# tiny13_charlie4_50mm_boosted_optical_dia.net
KiCad netlist of a schematic drawn in EAGLE
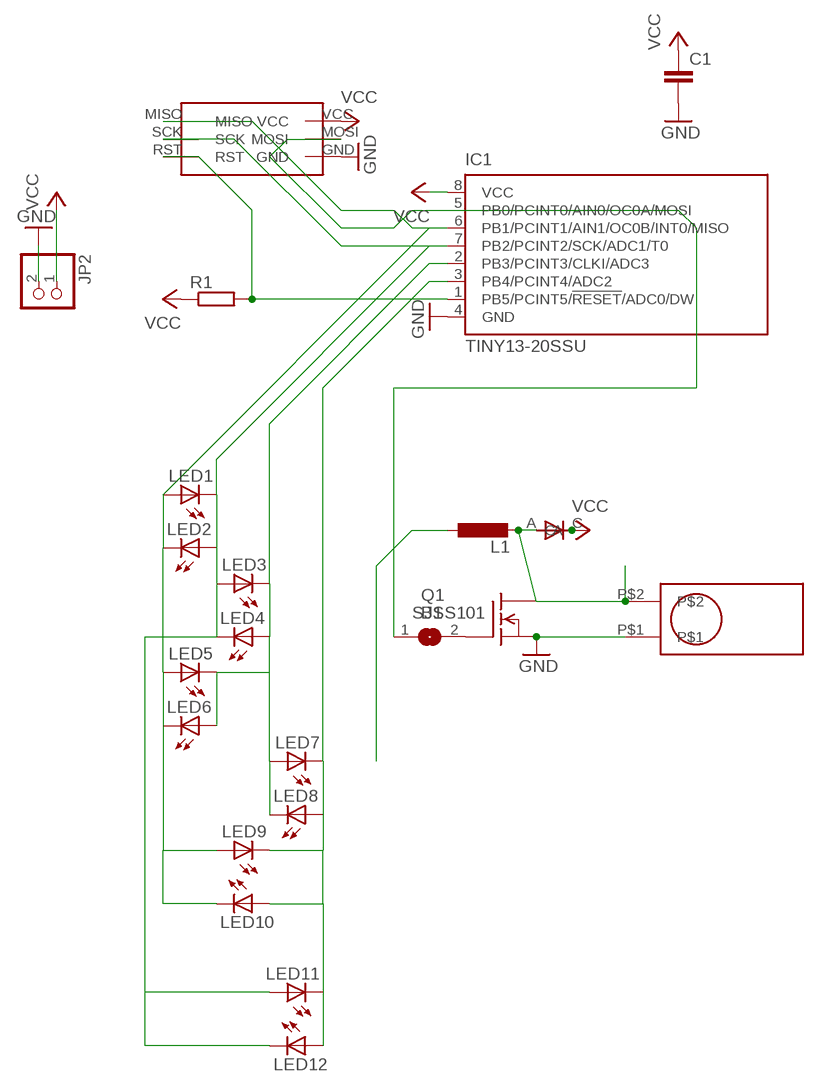
[diagram p0: schematic, sheet 1]

(export (version "E")
  (design (tool "Eeschema 10.0.6"))
  (components
    (comp (ref "C1")
      (value "C-EU025-025X050")
      (footprint "eagle-import:C025-025X050")
      (libsource (lib "eagle-import") (part "C-EU025-025X050"))
    )
    (comp (ref "IC1")
      (value "TINY13-20SSU")
      (footprint "eagle-import:8S1")
      (fields (field (name "MPN") "ATTINY13-20SSU"))
      (libsource (lib "eagle-import") (part "TINY13SSU-20"))
    )
    (comp (ref "JP2")
      (value "PINHD-1X2")
      (footprint "eagle-import:1X02")
      (libsource (lib "eagle-import") (part "PINHD-1X2"))
    )
    (comp (ref "L1")
      (value "L-EU0204/5")
      (footprint "eagle-import:0204_5")
      (libsource (lib "eagle-import") (part "L-EU0204/5"))
    )
    (comp (ref "LED1")
      (value "LED3MM")
      (footprint "eagle-import:LED3MM")
      (libsource (lib "eagle-import") (part "LED3MM"))
    )
    (comp (ref "LED2")
      (value "LED3MM")
      (footprint "eagle-import:LED3MM")
      (libsource (lib "eagle-import") (part "LED3MM"))
    )
    (comp (ref "LED3")
      (value "LED3MM")
      (footprint "eagle-import:LED3MM")
      (libsource (lib "eagle-import") (part "LED3MM"))
    )
    (comp (ref "LED4")
      (value "LED3MM")
      (footprint "eagle-import:LED3MM")
      (libsource (lib "eagle-import") (part "LED3MM"))
    )
    (comp (ref "LED5")
      (value "LED3MM")
      (footprint "eagle-import:LED3MM")
      (libsource (lib "eagle-import") (part "LED3MM"))
    )
    (comp (ref "LED6")
      (value "LED3MM")
      (footprint "eagle-import:LED3MM")
      (libsource (lib "eagle-import") (part "LED3MM"))
    )
    (comp (ref "LED7")
      (value "LED3MM")
      (footprint "eagle-import:LED3MM")
      (libsource (lib "eagle-import") (part "LED3MM"))
    )
    (comp (ref "LED8")
      (value "LED3MM")
      (footprint "eagle-import:LED3MM")
      (libsource (lib "eagle-import") (part "LED3MM"))
    )
    (comp (ref "LED9")
      (value "LED3MM")
      (footprint "eagle-import:LED3MM")
      (libsource (lib "eagle-import") (part "LED3MM"))
    )
    (comp (ref "LED10")
      (value "LED3MM")
      (footprint "eagle-import:LED3MM")
      (libsource (lib "eagle-import") (part "LED3MM"))
    )
    (comp (ref "LED11")
      (value "LED3MM")
      (footprint "eagle-import:LED3MM")
      (libsource (lib "eagle-import") (part "LED3MM"))
    )
    (comp (ref "LED12")
      (value "LED3MM")
      (footprint "eagle-import:LED3MM")
      (libsource (lib "eagle-import") (part "LED3MM"))
    )
    (comp (ref "Q1")
      (value "BSS101")
      (footprint "eagle-import:TO92")
      (libsource (lib "eagle-import") (part "BSS101"))
    )
    (comp (ref "R1")
      (value "R-EU_0204/5")
      (footprint "eagle-import:0204_5")
      (libsource (lib "eagle-import") (part "R-EU_0204/5"))
    )
    (comp (ref "SJ1") (value "SJ") (footprint "eagle-import:SJ") (libsource (lib "eagle-import") (part "SJ")))
    (comp (ref "U$1")
      (value "TILT_SWITCH_MECHANICAL")
      (footprint "eagle-import:TILT_SWITCH_MECHANICAL")
      (libsource (lib "eagle-import") (part "TILT_SWITCH_MECHANICAL"))
    )
    (comp (ref "U$2")
      (value "AVR_ISP_6_PIN_1X6_SMT_CONTACT_PROGRAMMER")
      (footprint "eagle-import:CONTACT_ISP_PROGRAMMER_1X6_ATMEL_2")
      (libsource (lib "eagle-import") (part "AVR_ISP_6_PIN_1X6_SMT_CONTACT_PROGRAMMER"))
    )
    (comp (ref "U$3")
      (value "D-6")
      (footprint "eagle-import:D-7.5")
      (libsource (lib "eagle-import") (part "D-6"))
    )
  )
  (nets
    (net (code "1") (name "GND") (class "Default")
      (node (ref "C1") (pin "2") (pinfunction "2_2") (pintype "passive"))
      (node (ref "IC1") (pin "4") (pinfunction "GND_4") (pintype "power_in"))
      (node (ref "JP2") (pin "2") (pinfunction "2_2") (pintype "passive"))
      (node (ref "Q1") (pin "1") (pinfunction "S_1") (pintype "passive"))
      (node (ref "U$1") (pin "P$1") (pinfunction "P$1_P$1") (pintype "bidirectional"))
      (node (ref "U$2") (pin "GND") (pinfunction "GND_GND") (pintype "bidirectional"))
    )
    (net (code "2") (name "Net-(IC1-PB0{slash}PCINT0{slash}AIN0{slash}OC0A{slash}MOSI)") (class "Default")
      (node (ref "IC1") (pin "5") (pinfunction "PB0/PCINT0/AIN0/OC0A/MOSI_5") (pintype "bidirectional"))
      (node (ref "SJ1") (pin "1") (pinfunction "1_1") (pintype "passive"))
      (node (ref "U$2") (pin "MOSI") (pinfunction "MOSI_MOSI") (pintype "bidirectional"))
    )
    (net (code "3") (name "Net-(IC1-PB1{slash}PCINT1{slash}AIN1{slash}OC0B{slash}INT0{slash}MISO)") (class "Default")
      (node (ref "IC1") (pin "6") (pinfunction "PB1/PCINT1/AIN1/OC0B/INT0/MISO_6") (pintype "bidirectional"))
      (node (ref "LED1") (pin "A") (pinfunction "A_A") (pintype "passive"))
      (node (ref "LED10") (pin "K") (pinfunction "C_K") (pintype "passive"))
      (node (ref "LED2") (pin "K") (pinfunction "C_K") (pintype "passive"))
      (node (ref "LED5") (pin "A") (pinfunction "A_A") (pintype "passive"))
      (node (ref "LED6") (pin "K") (pinfunction "C_K") (pintype "passive"))
      (node (ref "LED9") (pin "A") (pinfunction "A_A") (pintype "passive"))
      (node (ref "U$2") (pin "MISO") (pinfunction "MISO_MISO") (pintype "bidirectional"))
    )
    (net (code "4") (name "Net-(IC1-PB2{slash}PCINT2{slash}SCK{slash}ADC1{slash}T0)") (class "Default")
      (node (ref "IC1") (pin "7") (pinfunction "PB2/PCINT2/SCK/ADC1/T0_7") (pintype "bidirectional"))
      (node (ref "LED1") (pin "K") (pinfunction "C_K") (pintype "passive"))
      (node (ref "LED11") (pin "A") (pinfunction "A_A") (pintype "passive"))
      (node (ref "LED12") (pin "K") (pinfunction "C_K") (pintype "passive"))
      (node (ref "LED2") (pin "A") (pinfunction "A_A") (pintype "passive"))
      (node (ref "LED3") (pin "A") (pinfunction "A_A") (pintype "passive"))
      (node (ref "LED4") (pin "K") (pinfunction "C_K") (pintype "passive"))
      (node (ref "U$2") (pin "SCK") (pinfunction "SCK_SCK") (pintype "bidirectional"))
    )
    (net (code "5") (name "Net-(IC1-PB3{slash}PCINT3{slash}CLKI{slash}ADC3)") (class "Default")
      (node (ref "IC1") (pin "2") (pinfunction "PB3/PCINT3/CLKI/ADC3_2") (pintype "bidirectional"))
      (node (ref "LED3") (pin "K") (pinfunction "C_K") (pintype "passive"))
      (node (ref "LED4") (pin "A") (pinfunction "A_A") (pintype "passive"))
      (node (ref "LED5") (pin "K") (pinfunction "C_K") (pintype "passive"))
      (node (ref "LED6") (pin "A") (pinfunction "A_A") (pintype "passive"))
      (node (ref "LED7") (pin "A") (pinfunction "A_A") (pintype "passive"))
      (node (ref "LED8") (pin "K") (pinfunction "C_K") (pintype "passive"))
    )
    (net (code "6") (name "Net-(IC1-PB4{slash}PCINT4{slash}ADC2)") (class "Default")
      (node (ref "IC1") (pin "3") (pinfunction "PB4/PCINT4/ADC2_3") (pintype "bidirectional"))
      (node (ref "LED10") (pin "A") (pinfunction "A_A") (pintype "passive"))
      (node (ref "LED11") (pin "K") (pinfunction "C_K") (pintype "passive"))
      (node (ref "LED12") (pin "A") (pinfunction "A_A") (pintype "passive"))
      (node (ref "LED7") (pin "K") (pinfunction "C_K") (pintype "passive"))
      (node (ref "LED8") (pin "A") (pinfunction "A_A") (pintype "passive"))
      (node (ref "LED9") (pin "K") (pinfunction "C_K") (pintype "passive"))
    )
    (net (code "7") (name "Net-(IC1-PB5{slash}PCINT5{slash}~{RESET}{slash}ADC0{slash}DW)") (class "Default")
      (node (ref "IC1") (pin "1") (pinfunction "PB5/PCINT5/~{RESET}/ADC0/DW_1") (pintype "bidirectional"))
      (node (ref "R1") (pin "2") (pinfunction "2_2") (pintype "passive"))
      (node (ref "U$2") (pin "RST") (pinfunction "RST_RST") (pintype "bidirectional"))
    )
    (net (code "8") (name "Net-(Q1-D)") (class "Default")
      (node (ref "L1") (pin "2") (pinfunction "2_2") (pintype "passive"))
      (node (ref "Q1") (pin "3") (pinfunction "D_3") (pintype "passive"))
      (node (ref "U$1") (pin "P$2") (pinfunction "P$2_P$2") (pintype "bidirectional"))
      (node (ref "U$3") (pin "A") (pinfunction "A_A") (pintype "bidirectional"))
    )
    (net (code "9") (name "Net-(Q1-G)") (class "Default")
      (node (ref "Q1") (pin "2") (pinfunction "G_2") (pintype "passive"))
      (node (ref "SJ1") (pin "2") (pinfunction "2_2") (pintype "passive"))
    )
    (net (code "10") (name "VCC") (class "Default")
      (node (ref "C1") (pin "1") (pinfunction "1_1") (pintype "passive"))
      (node (ref "IC1") (pin "8") (pinfunction "VCC_8") (pintype "power_in"))
      (node (ref "JP2") (pin "1") (pinfunction "1_1") (pintype "passive"))
      (node (ref "R1") (pin "1") (pinfunction "1_1") (pintype "passive"))
      (node (ref "U$2") (pin "VCC") (pinfunction "VCC_VCC") (pintype "bidirectional"))
      (node (ref "U$3") (pin "C") (pinfunction "C_C") (pintype "bidirectional"))
    )
    (net (code "11") (name "unconnected-(L1-Pad1)") (class "Default")
      (node (ref "L1") (pin "1") (pinfunction "1_1") (pintype "passive"))
    )
  )
)
